# FPGA_IO_Transceiver.net
KiCad netlist of a schematic drawn in Altium Designer
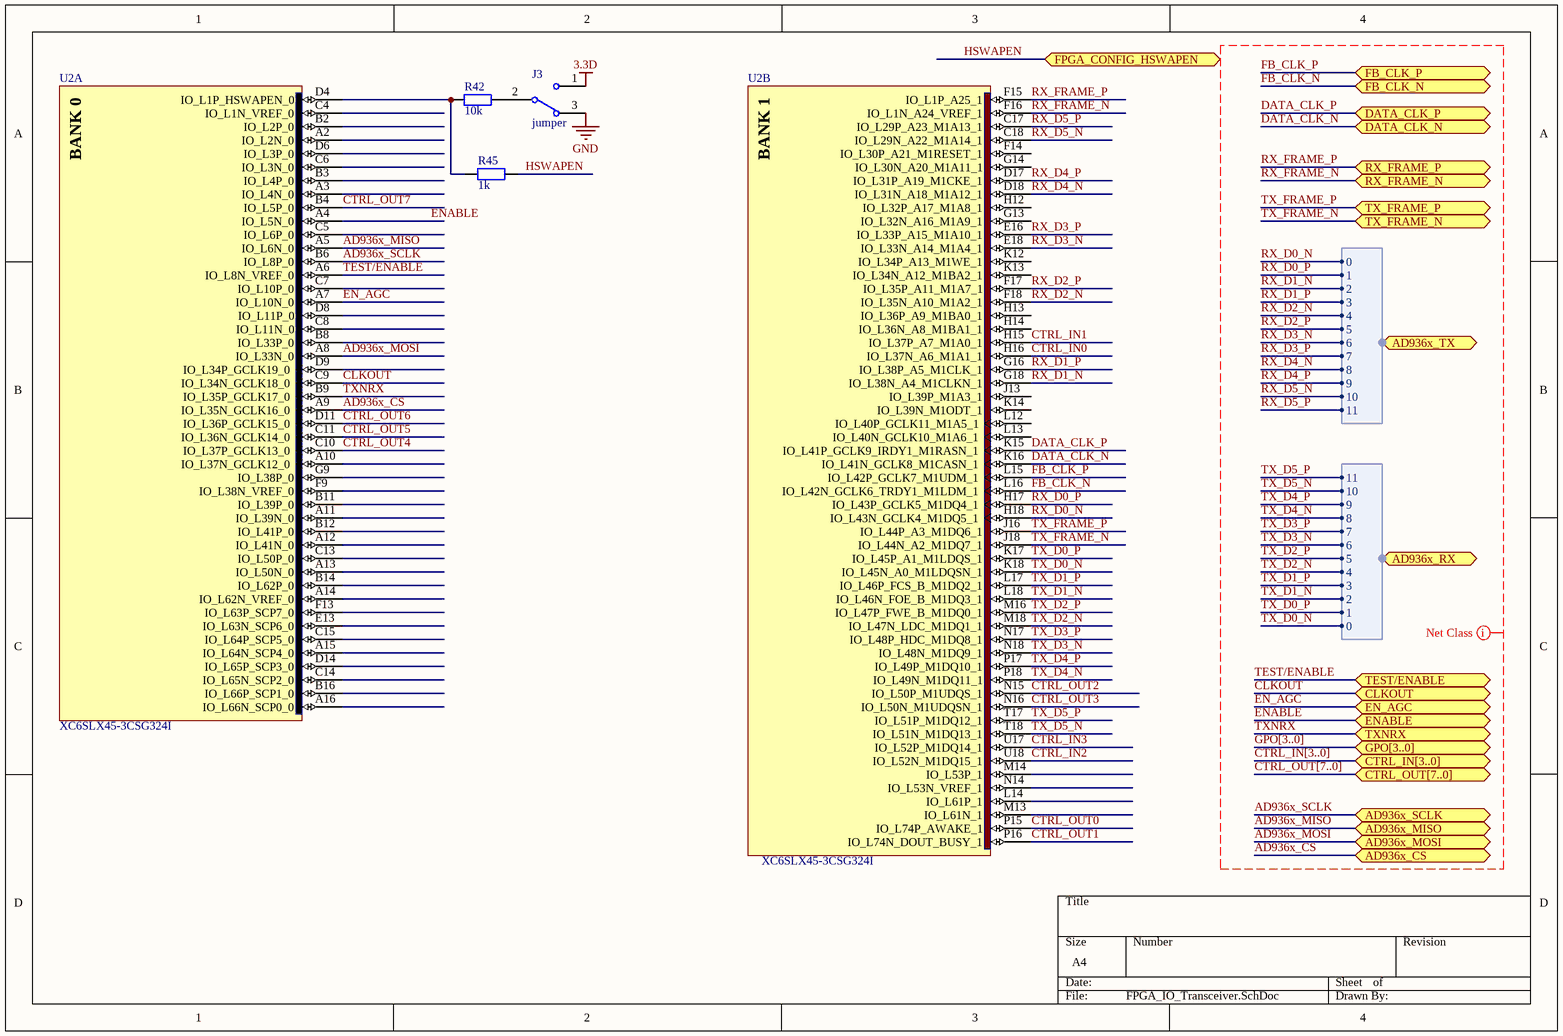
[diagram p0: FPGA_IO_Transceiver.SchDoc]

(export (version "E")
  (design (tool "Eeschema 10.0.6"))
  (components
    (comp (ref "J3")
      (value "jumper")
      (footprint "0402J")
      (description "SPDT Subminiature Toggle Switch, Right Angle Mounting, Vertical Actuation")
      (fields (field (name "PUBLISHER") "Altium Limited"))
      (libsource (lib "Miscellaneous Devices") (part "SW-SPDT"))
    )
    (comp (ref "R42")
      (value "10k")
      (footprint "0402")
      (description "Resistor")
      (fields (field (name "PUBLISHER") "Altium Limited"))
      (libsource (lib "RTC6705") (part "Res2"))
    )
    (comp (ref "R45")
      (value "1k")
      (footprint "0402")
      (description "Resistor")
      (fields (field (name "PUBLISHER") "Altium Limited"))
      (libsource (lib "RTC6705") (part "Res2"))
    )
    (comp (ref "U2")
      (value "XC6SLX45-3CSG324I")
      (footprint "CSG324")
      (fields (field (name "PUBLISHER") "Altium Limited"))
      (libsource (lib "Xilinx Spartan-6") (part "XC6SLX45-3CSG324I"))
    )
  )
  (nets
    (net (code "6") (name "/AD936x_CS") (class "Default")
      (node (ref "U2") (pin "A9") (pinfunction "IO_L35N_GCLK16_0_A9") (pintype "bidirectional"))
    )
    (net (code "7") (name "/AD936x_MISO") (class "Default")
      (node (ref "U2") (pin "A5") (pinfunction "IO_L6N_0_A5") (pintype "bidirectional"))
    )
    (net (code "8") (name "/AD936x_MOSI") (class "Default")
      (node (ref "U2") (pin "A8") (pinfunction "IO_L33N_0_A8") (pintype "bidirectional"))
    )
    (net (code "9") (name "/AD936x_SCLK") (class "Default")
      (node (ref "U2") (pin "B6") (pinfunction "IO_L8P_0_B6") (pintype "bidirectional"))
    )
    (net (code "10") (name "/CLKOUT") (class "Default")
      (node (ref "U2") (pin "C9") (pinfunction "IO_L34N_GCLK18_0_C9") (pintype "bidirectional"))
    )
    (net (code "11") (name "/CTRL_IN0") (class "Default")
      (node (ref "U2") (pin "H16") (pinfunction "IO_L37N_A6_M1A1_1_H16") (pintype "bidirectional"))
    )
    (net (code "12") (name "/CTRL_IN1") (class "Default")
      (node (ref "U2") (pin "H15") (pinfunction "IO_L37P_A7_M1A0_1_H15") (pintype "bidirectional"))
    )
    (net (code "13") (name "/CTRL_IN2") (class "Default")
      (node (ref "U2") (pin "U18") (pinfunction "IO_L52N_M1DQ15_1_U18") (pintype "bidirectional"))
    )
    (net (code "14") (name "/CTRL_IN3") (class "Default")
      (node (ref "U2") (pin "U17") (pinfunction "IO_L52P_M1DQ14_1_U17") (pintype "bidirectional"))
    )
    (net (code "16") (name "/CTRL_OUT0") (class "Default")
      (node (ref "U2") (pin "P15") (pinfunction "IO_L74P_AWAKE_1_P15") (pintype "bidirectional"))
    )
    (net (code "17") (name "/CTRL_OUT1") (class "Default")
      (node (ref "U2") (pin "P16") (pinfunction "IO_L74N_DOUT_BUSY_1_P16") (pintype "bidirectional"))
    )
    (net (code "18") (name "/CTRL_OUT2") (class "Default")
      (node (ref "U2") (pin "N15") (pinfunction "IO_L50P_M1UDQS_1_N15") (pintype "bidirectional"))
    )
    (net (code "19") (name "/CTRL_OUT3") (class "Default")
      (node (ref "U2") (pin "N16") (pinfunction "IO_L50N_M1UDQSN_1_N16") (pintype "bidirectional"))
    )
    (net (code "20") (name "/CTRL_OUT4") (class "Default")
      (node (ref "U2") (pin "C10") (pinfunction "IO_L37P_GCLK13_0_C10") (pintype "bidirectional"))
    )
    (net (code "21") (name "/CTRL_OUT5") (class "Default")
      (node (ref "U2") (pin "C11") (pinfunction "IO_L36N_GCLK14_0_C11") (pintype "bidirectional"))
    )
    (net (code "22") (name "/CTRL_OUT6") (class "Default")
      (node (ref "U2") (pin "D11") (pinfunction "IO_L36P_GCLK15_0_D11") (pintype "bidirectional"))
    )
    (net (code "23") (name "/CTRL_OUT7") (class "Default")
      (node (ref "U2") (pin "B4") (pinfunction "IO_L5P_0_B4") (pintype "bidirectional"))
    )
    (net (code "25") (name "/DATA_CLK_N") (class "Default")
      (node (ref "U2") (pin "K16") (pinfunction "IO_L41N_GCLK8_M1CASN_1_K16") (pintype "bidirectional"))
    )
    (net (code "26") (name "/DATA_CLK_P") (class "Default")
      (node (ref "U2") (pin "K15") (pinfunction "IO_L41P_GCLK9_IRDY1_M1RASN_1_K15") (pintype "bidirectional"))
    )
    (net (code "27") (name "/ENABLE") (class "Default")
      (node (ref "U2") (pin "A4") (pinfunction "IO_L5N_0_A4") (pintype "bidirectional"))
    )
    (net (code "28") (name "/EN_AGC") (class "Default")
      (node (ref "U2") (pin "A7") (pinfunction "IO_L10N_0_A7") (pintype "bidirectional"))
    )
    (net (code "29") (name "/FB_CLK_N") (class "Default")
      (node (ref "U2") (pin "L16") (pinfunction "IO_L42N_GCLK6_TRDY1_M1LDM_1_L16") (pintype "bidirectional"))
    )
    (net (code "30") (name "/FB_CLK_P") (class "Default")
      (node (ref "U2") (pin "L15") (pinfunction "IO_L42P_GCLK7_M1UDM_1_L15") (pintype "bidirectional"))
    )
    (net (code "32") (name "/HSWAPEN") (class "Default")
      (node (ref "R45") (pin "1") (pinfunction "1_1") (pintype "passive"))
    )
    (net (code "33") (name "/RX_D0_N") (class "Default")
      (node (ref "U2") (pin "H18") (pinfunction "IO_L43N_GCLK4_M1DQ5_1_H18") (pintype "bidirectional"))
    )
    (net (code "34") (name "/RX_D0_P") (class "Default")
      (node (ref "U2") (pin "H17") (pinfunction "IO_L43P_GCLK5_M1DQ4_1_H17") (pintype "bidirectional"))
    )
    (net (code "35") (name "/RX_D1_N") (class "Default")
      (node (ref "U2") (pin "G18") (pinfunction "IO_L38N_A4_M1CLKN_1_G18") (pintype "bidirectional"))
    )
    (net (code "36") (name "/RX_D1_P") (class "Default")
      (node (ref "U2") (pin "G16") (pinfunction "IO_L38P_A5_M1CLK_1_G16") (pintype "bidirectional"))
    )
    (net (code "37") (name "/RX_D2_N") (class "Default")
      (node (ref "U2") (pin "F18") (pinfunction "IO_L35N_A10_M1A2_1_F18") (pintype "bidirectional"))
    )
    (net (code "38") (name "/RX_D2_P") (class "Default")
      (node (ref "U2") (pin "F17") (pinfunction "IO_L35P_A11_M1A7_1_F17") (pintype "bidirectional"))
    )
    (net (code "39") (name "/RX_D3_N") (class "Default")
      (node (ref "U2") (pin "E18") (pinfunction "IO_L33N_A14_M1A4_1_E18") (pintype "bidirectional"))
    )
    (net (code "40") (name "/RX_D3_P") (class "Default")
      (node (ref "U2") (pin "E16") (pinfunction "IO_L33P_A15_M1A10_1_E16") (pintype "bidirectional"))
    )
    (net (code "41") (name "/RX_D4_N") (class "Default")
      (node (ref "U2") (pin "D18") (pinfunction "IO_L31N_A18_M1A12_1_D18") (pintype "bidirectional"))
    )
    (net (code "42") (name "/RX_D4_P") (class "Default")
      (node (ref "U2") (pin "D17") (pinfunction "IO_L31P_A19_M1CKE_1_D17") (pintype "bidirectional"))
    )
    (net (code "43") (name "/RX_D5_N") (class "Default")
      (node (ref "U2") (pin "C18") (pinfunction "IO_L29N_A22_M1A14_1_C18") (pintype "bidirectional"))
    )
    (net (code "44") (name "/RX_D5_P") (class "Default")
      (node (ref "U2") (pin "C17") (pinfunction "IO_L29P_A23_M1A13_1_C17") (pintype "bidirectional"))
    )
    (net (code "45") (name "/RX_FRAME_N") (class "Default")
      (node (ref "U2") (pin "F16") (pinfunction "IO_L1N_A24_VREF_1_F16") (pintype "bidirectional"))
    )
    (net (code "46") (name "/RX_FRAME_P") (class "Default")
      (node (ref "U2") (pin "F15") (pinfunction "IO_L1P_A25_1_F15") (pintype "bidirectional"))
    )
    (net (code "47") (name "/TEST{slash}ENABLE") (class "Default")
      (node (ref "U2") (pin "A6") (pinfunction "IO_L8N_VREF_0_A6") (pintype "bidirectional"))
    )
    (net (code "48") (name "/TXNRX") (class "Default")
      (node (ref "U2") (pin "B9") (pinfunction "IO_L35P_GCLK17_0_B9") (pintype "bidirectional"))
    )
    (net (code "49") (name "/TX_D0_N") (class "Default")
      (node (ref "U2") (pin "K18") (pinfunction "IO_L45N_A0_M1LDQSN_1_K18") (pintype "bidirectional"))
    )
    (net (code "50") (name "/TX_D0_P") (class "Default")
      (node (ref "U2") (pin "K17") (pinfunction "IO_L45P_A1_M1LDQS_1_K17") (pintype "bidirectional"))
    )
    (net (code "51") (name "/TX_D1_N") (class "Default")
      (node (ref "U2") (pin "L18") (pinfunction "IO_L46N_FOE_B_M1DQ3_1_L18") (pintype "bidirectional"))
    )
    (net (code "52") (name "/TX_D1_P") (class "Default")
      (node (ref "U2") (pin "L17") (pinfunction "IO_L46P_FCS_B_M1DQ2_1_L17") (pintype "bidirectional"))
    )
    (net (code "53") (name "/TX_D2_N") (class "Default")
      (node (ref "U2") (pin "M18") (pinfunction "IO_L47N_LDC_M1DQ1_1_M18") (pintype "bidirectional"))
    )
    (net (code "54") (name "/TX_D2_P") (class "Default")
      (node (ref "U2") (pin "M16") (pinfunction "IO_L47P_FWE_B_M1DQ0_1_M16") (pintype "bidirectional"))
    )
    (net (code "55") (name "/TX_D3_N") (class "Default")
      (node (ref "U2") (pin "N18") (pinfunction "IO_L48N_M1DQ9_1_N18") (pintype "bidirectional"))
    )
    (net (code "56") (name "/TX_D3_P") (class "Default")
      (node (ref "U2") (pin "N17") (pinfunction "IO_L48P_HDC_M1DQ8_1_N17") (pintype "bidirectional"))
    )
    (net (code "57") (name "/TX_D4_N") (class "Default")
      (node (ref "U2") (pin "P18") (pinfunction "IO_L49N_M1DQ11_1_P18") (pintype "bidirectional"))
    )
    (net (code "58") (name "/TX_D4_P") (class "Default")
      (node (ref "U2") (pin "P17") (pinfunction "IO_L49P_M1DQ10_1_P17") (pintype "bidirectional"))
    )
    (net (code "59") (name "/TX_D5_N") (class "Default")
      (node (ref "U2") (pin "T18") (pinfunction "IO_L51N_M1DQ13_1_T18") (pintype "bidirectional"))
    )
    (net (code "60") (name "/TX_D5_P") (class "Default")
      (node (ref "U2") (pin "T17") (pinfunction "IO_L51P_M1DQ12_1_T17") (pintype "bidirectional"))
    )
    (net (code "61") (name "/TX_FRAME_N") (class "Default")
      (node (ref "U2") (pin "J18") (pinfunction "IO_L44N_A2_M1DQ7_1_J18") (pintype "bidirectional"))
    )
    (net (code "62") (name "/TX_FRAME_P") (class "Default")
      (node (ref "U2") (pin "J16") (pinfunction "IO_L44P_A3_M1DQ6_1_J16") (pintype "bidirectional"))
    )
    (net (code "64") (name "3.3D") (class "Default")
      (node (ref "J3") (pin "1") (pinfunction "1_1") (pintype "passive"))
    )
    (net (code "65") (name "GND") (class "Default")
      (node (ref "J3") (pin "3") (pinfunction "3_3") (pintype "passive"))
    )
    (net (code "66") (name "Net-(J3-Pad2)") (class "Default")
      (node (ref "J3") (pin "2") (pinfunction "2_2") (pintype "passive"))
      (node (ref "R42") (pin "1") (pinfunction "1_1") (pintype "passive"))
    )
    (net (code "67") (name "Net-(U2A-IO_L1P_HSWAPEN_0)") (class "Default")
      (node (ref "R42") (pin "2") (pinfunction "2_2") (pintype "passive"))
      (node (ref "R45") (pin "2") (pinfunction "2_2") (pintype "passive"))
      (node (ref "U2") (pin "D4") (pinfunction "IO_L1P_HSWAPEN_0_D4") (pintype "bidirectional"))
    )
    (net (code "68") (name "unconnected-(U2A-IO_L1N_VREF_0-PadC4)") (class "Default")
      (node (ref "U2") (pin "C4") (pinfunction "IO_L1N_VREF_0_C4") (pintype "bidirectional"))
    )
    (net (code "69") (name "unconnected-(U2A-IO_L2N_0-PadA2)") (class "Default")
      (node (ref "U2") (pin "A2") (pinfunction "IO_L2N_0_A2") (pintype "bidirectional"))
    )
    (net (code "70") (name "unconnected-(U2A-IO_L2P_0-PadB2)") (class "Default")
      (node (ref "U2") (pin "B2") (pinfunction "IO_L2P_0_B2") (pintype "bidirectional"))
    )
    (net (code "71") (name "unconnected-(U2A-IO_L3N_0-PadC6)") (class "Default")
      (node (ref "U2") (pin "C6") (pinfunction "IO_L3N_0_C6") (pintype "bidirectional"))
    )
    (net (code "72") (name "unconnected-(U2A-IO_L3P_0-PadD6)") (class "Default")
      (node (ref "U2") (pin "D6") (pinfunction "IO_L3P_0_D6") (pintype "bidirectional"))
    )
    (net (code "73") (name "unconnected-(U2A-IO_L4N_0-PadA3)") (class "Default")
      (node (ref "U2") (pin "A3") (pinfunction "IO_L4N_0_A3") (pintype "bidirectional"))
    )
    (net (code "74") (name "unconnected-(U2A-IO_L4P_0-PadB3)") (class "Default")
      (node (ref "U2") (pin "B3") (pinfunction "IO_L4P_0_B3") (pintype "bidirectional"))
    )
    (net (code "75") (name "unconnected-(U2A-IO_L6P_0-PadC5)") (class "Default")
      (node (ref "U2") (pin "C5") (pinfunction "IO_L6P_0_C5") (pintype "bidirectional"))
    )
    (net (code "76") (name "unconnected-(U2A-IO_L10P_0-PadC7)") (class "Default")
      (node (ref "U2") (pin "C7") (pinfunction "IO_L10P_0_C7") (pintype "bidirectional"))
    )
    (net (code "77") (name "unconnected-(U2A-IO_L11N_0-PadC8)") (class "Default")
      (node (ref "U2") (pin "C8") (pinfunction "IO_L11N_0_C8") (pintype "bidirectional"))
    )
    (net (code "78") (name "unconnected-(U2A-IO_L11P_0-PadD8)") (class "Default")
      (node (ref "U2") (pin "D8") (pinfunction "IO_L11P_0_D8") (pintype "bidirectional"))
    )
    (net (code "79") (name "unconnected-(U2A-IO_L33P_0-PadB8)") (class "Default")
      (node (ref "U2") (pin "B8") (pinfunction "IO_L33P_0_B8") (pintype "bidirectional"))
    )
    (net (code "80") (name "unconnected-(U2A-IO_L34P_GCLK19_0-PadD9)") (class "Default")
      (node (ref "U2") (pin "D9") (pinfunction "IO_L34P_GCLK19_0_D9") (pintype "bidirectional"))
    )
    (net (code "81") (name "unconnected-(U2A-IO_L37N_GCLK12_0-PadA10)") (class "Default")
      (node (ref "U2") (pin "A10") (pinfunction "IO_L37N_GCLK12_0_A10") (pintype "bidirectional"))
    )
    (net (code "82") (name "unconnected-(U2A-IO_L38N_VREF_0-PadF9)") (class "Default")
      (node (ref "U2") (pin "F9") (pinfunction "IO_L38N_VREF_0_F9") (pintype "bidirectional"))
    )
    (net (code "83") (name "unconnected-(U2A-IO_L38P_0-PadG9)") (class "Default")
      (node (ref "U2") (pin "G9") (pinfunction "IO_L38P_0_G9") (pintype "bidirectional"))
    )
    (net (code "84") (name "unconnected-(U2A-IO_L39N_0-PadA11)") (class "Default")
      (node (ref "U2") (pin "A11") (pinfunction "IO_L39N_0_A11") (pintype "bidirectional"))
    )
    (net (code "85") (name "unconnected-(U2A-IO_L39P_0-PadB11)") (class "Default")
      (node (ref "U2") (pin "B11") (pinfunction "IO_L39P_0_B11") (pintype "bidirectional"))
    )
    (net (code "86") (name "unconnected-(U2A-IO_L41N_0-PadA12)") (class "Default")
      (node (ref "U2") (pin "A12") (pinfunction "IO_L41N_0_A12") (pintype "bidirectional"))
    )
    (net (code "87") (name "unconnected-(U2A-IO_L41P_0-PadB12)") (class "Default")
      (node (ref "U2") (pin "B12") (pinfunction "IO_L41P_0_B12") (pintype "bidirectional"))
    )
    (net (code "88") (name "unconnected-(U2A-IO_L50N_0-PadA13)") (class "Default")
      (node (ref "U2") (pin "A13") (pinfunction "IO_L50N_0_A13") (pintype "bidirectional"))
    )
    (net (code "89") (name "unconnected-(U2A-IO_L50P_0-PadC13)") (class "Default")
      (node (ref "U2") (pin "C13") (pinfunction "IO_L50P_0_C13") (pintype "bidirectional"))
    )
    (net (code "90") (name "unconnected-(U2A-IO_L62N_VREF_0-PadA14)") (class "Default")
      (node (ref "U2") (pin "A14") (pinfunction "IO_L62N_VREF_0_A14") (pintype "bidirectional"))
    )
    (net (code "91") (name "unconnected-(U2A-IO_L62P_0-PadB14)") (class "Default")
      (node (ref "U2") (pin "B14") (pinfunction "IO_L62P_0_B14") (pintype "bidirectional"))
    )
    (net (code "92") (name "unconnected-(U2A-IO_L63N_SCP6_0-PadE13)") (class "Default")
      (node (ref "U2") (pin "E13") (pinfunction "IO_L63N_SCP6_0_E13") (pintype "bidirectional"))
    )
    (net (code "93") (name "unconnected-(U2A-IO_L63P_SCP7_0-PadF13)") (class "Default")
      (node (ref "U2") (pin "F13") (pinfunction "IO_L63P_SCP7_0_F13") (pintype "bidirectional"))
    )
    (net (code "94") (name "unconnected-(U2A-IO_L64N_SCP4_0-PadA15)") (class "Default")
      (node (ref "U2") (pin "A15") (pinfunction "IO_L64N_SCP4_0_A15") (pintype "bidirectional"))
    )
    (net (code "95") (name "unconnected-(U2A-IO_L64P_SCP5_0-PadC15)") (class "Default")
      (node (ref "U2") (pin "C15") (pinfunction "IO_L64P_SCP5_0_C15") (pintype "bidirectional"))
    )
    (net (code "96") (name "unconnected-(U2A-IO_L65N_SCP2_0-PadC14)") (class "Default")
      (node (ref "U2") (pin "C14") (pinfunction "IO_L65N_SCP2_0_C14") (pintype "bidirectional"))
    )
    (net (code "97") (name "unconnected-(U2A-IO_L65P_SCP3_0-PadD14)") (class "Default")
      (node (ref "U2") (pin "D14") (pinfunction "IO_L65P_SCP3_0_D14") (pintype "bidirectional"))
    )
    (net (code "98") (name "unconnected-(U2A-IO_L66N_SCP0_0-PadA16)") (class "Default")
      (node (ref "U2") (pin "A16") (pinfunction "IO_L66N_SCP0_0_A16") (pintype "bidirectional"))
    )
    (net (code "99") (name "unconnected-(U2A-IO_L66P_SCP1_0-PadB16)") (class "Default")
      (node (ref "U2") (pin "B16") (pinfunction "IO_L66P_SCP1_0_B16") (pintype "bidirectional"))
    )
    (net (code "100") (name "unconnected-(U2B-IO_L30N_A20_M1A11_1-PadG14)") (class "Default")
      (node (ref "U2") (pin "G14") (pinfunction "IO_L30N_A20_M1A11_1_G14") (pintype "bidirectional"))
    )
    (net (code "101") (name "unconnected-(U2B-IO_L30P_A21_M1RESET_1-PadF14)") (class "Default")
      (node (ref "U2") (pin "F14") (pinfunction "IO_L30P_A21_M1RESET_1_F14") (pintype "bidirectional"))
    )
    (net (code "102") (name "unconnected-(U2B-IO_L32N_A16_M1A9_1-PadG13)") (class "Default")
      (node (ref "U2") (pin "G13") (pinfunction "IO_L32N_A16_M1A9_1_G13") (pintype "bidirectional"))
    )
    (net (code "103") (name "unconnected-(U2B-IO_L32P_A17_M1A8_1-PadH12)") (class "Default")
      (node (ref "U2") (pin "H12") (pinfunction "IO_L32P_A17_M1A8_1_H12") (pintype "bidirectional"))
    )
    (net (code "104") (name "unconnected-(U2B-IO_L34N_A12_M1BA2_1-PadK13)") (class "Default")
      (node (ref "U2") (pin "K13") (pinfunction "IO_L34N_A12_M1BA2_1_K13") (pintype "bidirectional"))
    )
    (net (code "105") (name "unconnected-(U2B-IO_L34P_A13_M1WE_1-PadK12)") (class "Default")
      (node (ref "U2") (pin "K12") (pinfunction "IO_L34P_A13_M1WE_1_K12") (pintype "bidirectional"))
    )
    (net (code "106") (name "unconnected-(U2B-IO_L36N_A8_M1BA1_1-PadH14)") (class "Default")
      (node (ref "U2") (pin "H14") (pinfunction "IO_L36N_A8_M1BA1_1_H14") (pintype "bidirectional"))
    )
    (net (code "107") (name "unconnected-(U2B-IO_L36P_A9_M1BA0_1-PadH13)") (class "Default")
      (node (ref "U2") (pin "H13") (pinfunction "IO_L36P_A9_M1BA0_1_H13") (pintype "bidirectional"))
    )
    (net (code "108") (name "unconnected-(U2B-IO_L39N_M1ODT_1-PadK14)") (class "Default")
      (node (ref "U2") (pin "K14") (pinfunction "IO_L39N_M1ODT_1_K14") (pintype "bidirectional"))
    )
    (net (code "109") (name "unconnected-(U2B-IO_L39P_M1A3_1-PadJ13)") (class "Default")
      (node (ref "U2") (pin "J13") (pinfunction "IO_L39P_M1A3_1_J13") (pintype "bidirectional"))
    )
    (net (code "110") (name "unconnected-(U2B-IO_L40N_GCLK10_M1A6_1-PadL13)") (class "Default")
      (node (ref "U2") (pin "L13") (pinfunction "IO_L40N_GCLK10_M1A6_1_L13") (pintype "bidirectional"))
    )
    (net (code "111") (name "unconnected-(U2B-IO_L40P_GCLK11_M1A5_1-PadL12)") (class "Default")
      (node (ref "U2") (pin "L12") (pinfunction "IO_L40P_GCLK11_M1A5_1_L12") (pintype "bidirectional"))
    )
    (net (code "112") (name "unconnected-(U2B-IO_L53N_VREF_1-PadN14)") (class "Default")
      (node (ref "U2") (pin "N14") (pinfunction "IO_L53N_VREF_1_N14") (pintype "bidirectional"))
    )
    (net (code "113") (name "unconnected-(U2B-IO_L53P_1-PadM14)") (class "Default")
      (node (ref "U2") (pin "M14") (pinfunction "IO_L53P_1_M14") (pintype "bidirectional"))
    )
    (net (code "114") (name "unconnected-(U2B-IO_L61N_1-PadM13)") (class "Default")
      (node (ref "U2") (pin "M13") (pinfunction "IO_L61N_1_M13") (pintype "bidirectional"))
    )
    (net (code "115") (name "unconnected-(U2B-IO_L61P_1-PadL14)") (class "Default")
      (node (ref "U2") (pin "L14") (pinfunction "IO_L61P_1_L14") (pintype "bidirectional"))
    )
  )
)
